# hail.net
KiCad netlist of a schematic drawn in EAGLE
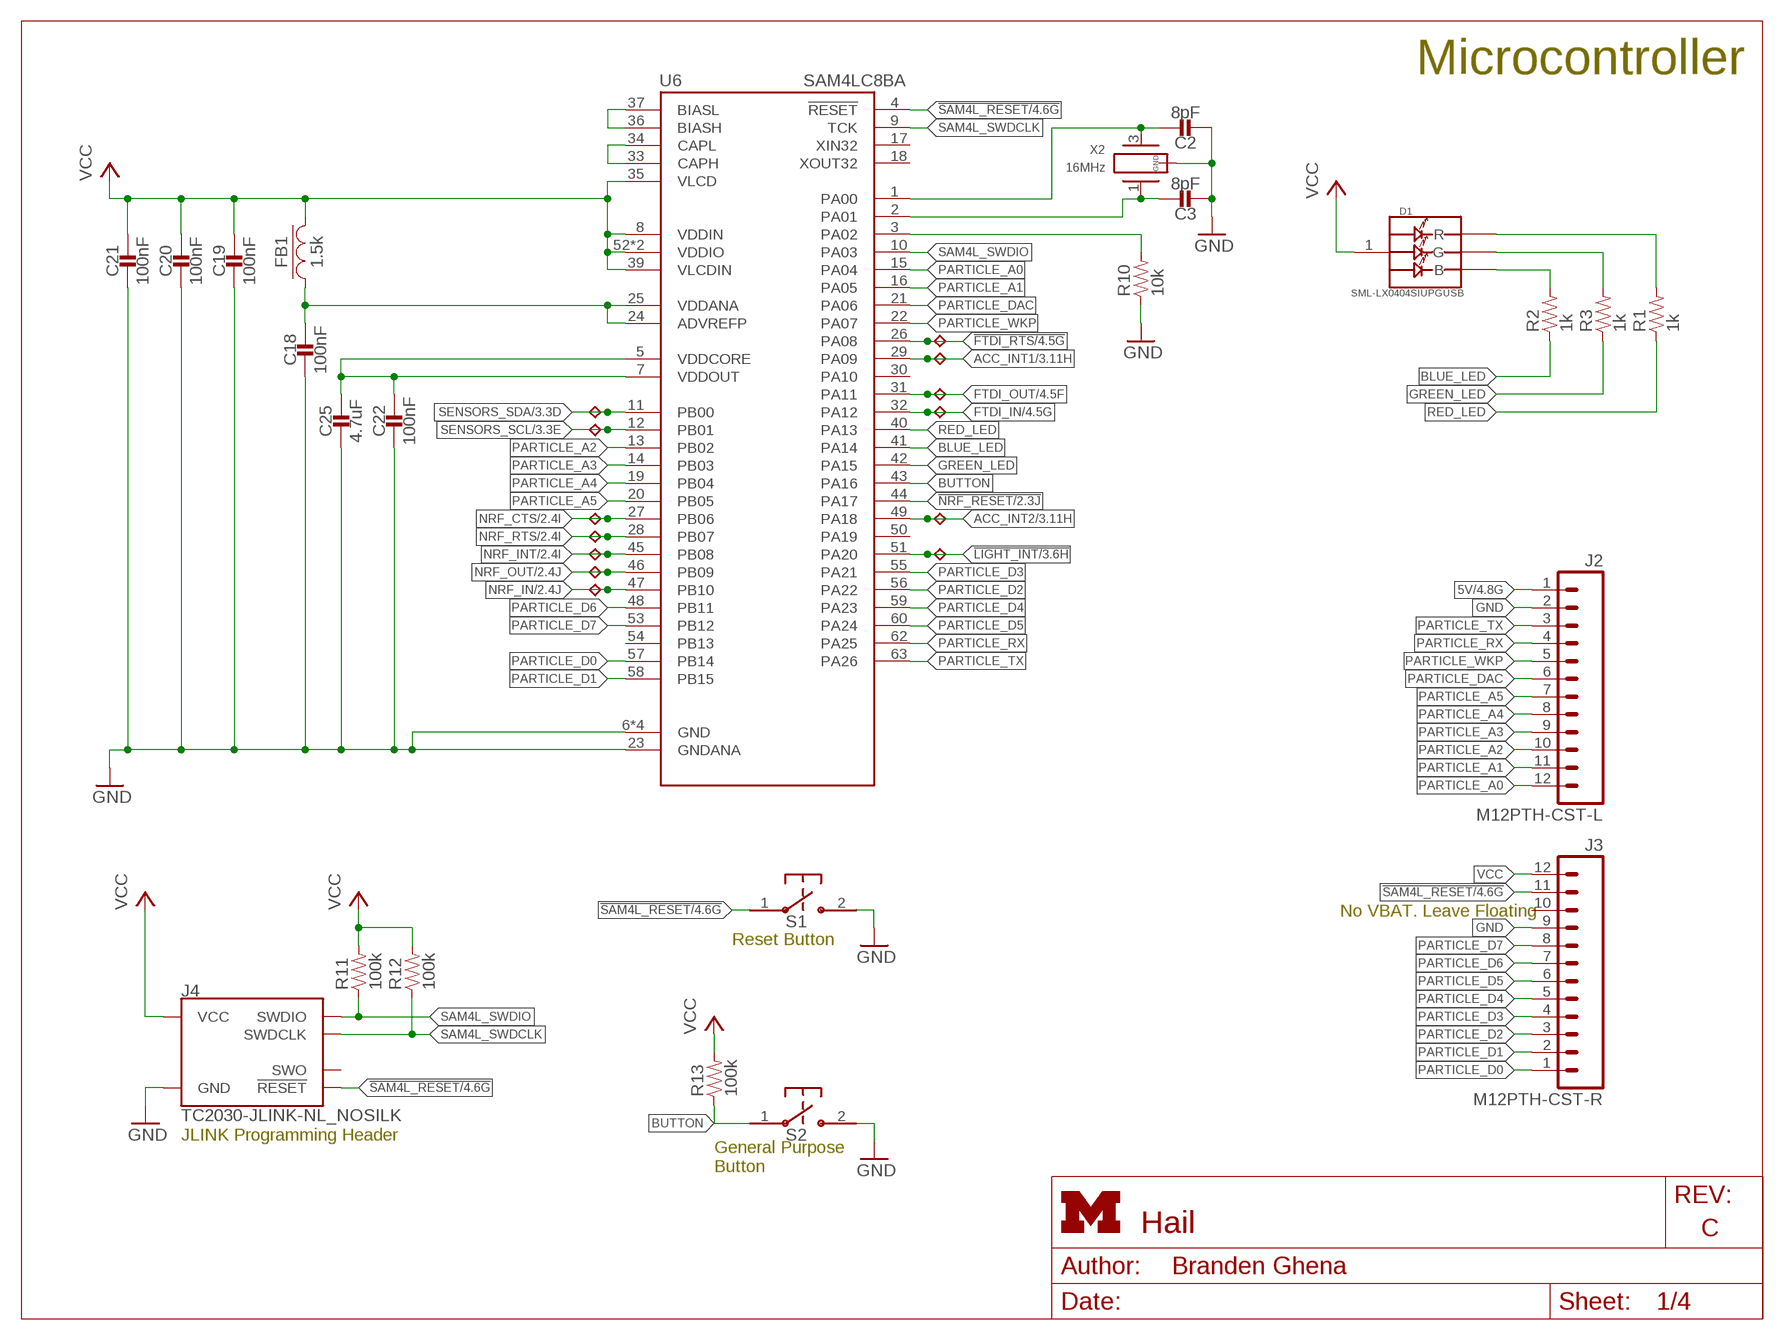
[diagram p0: schematic, sheet 1]
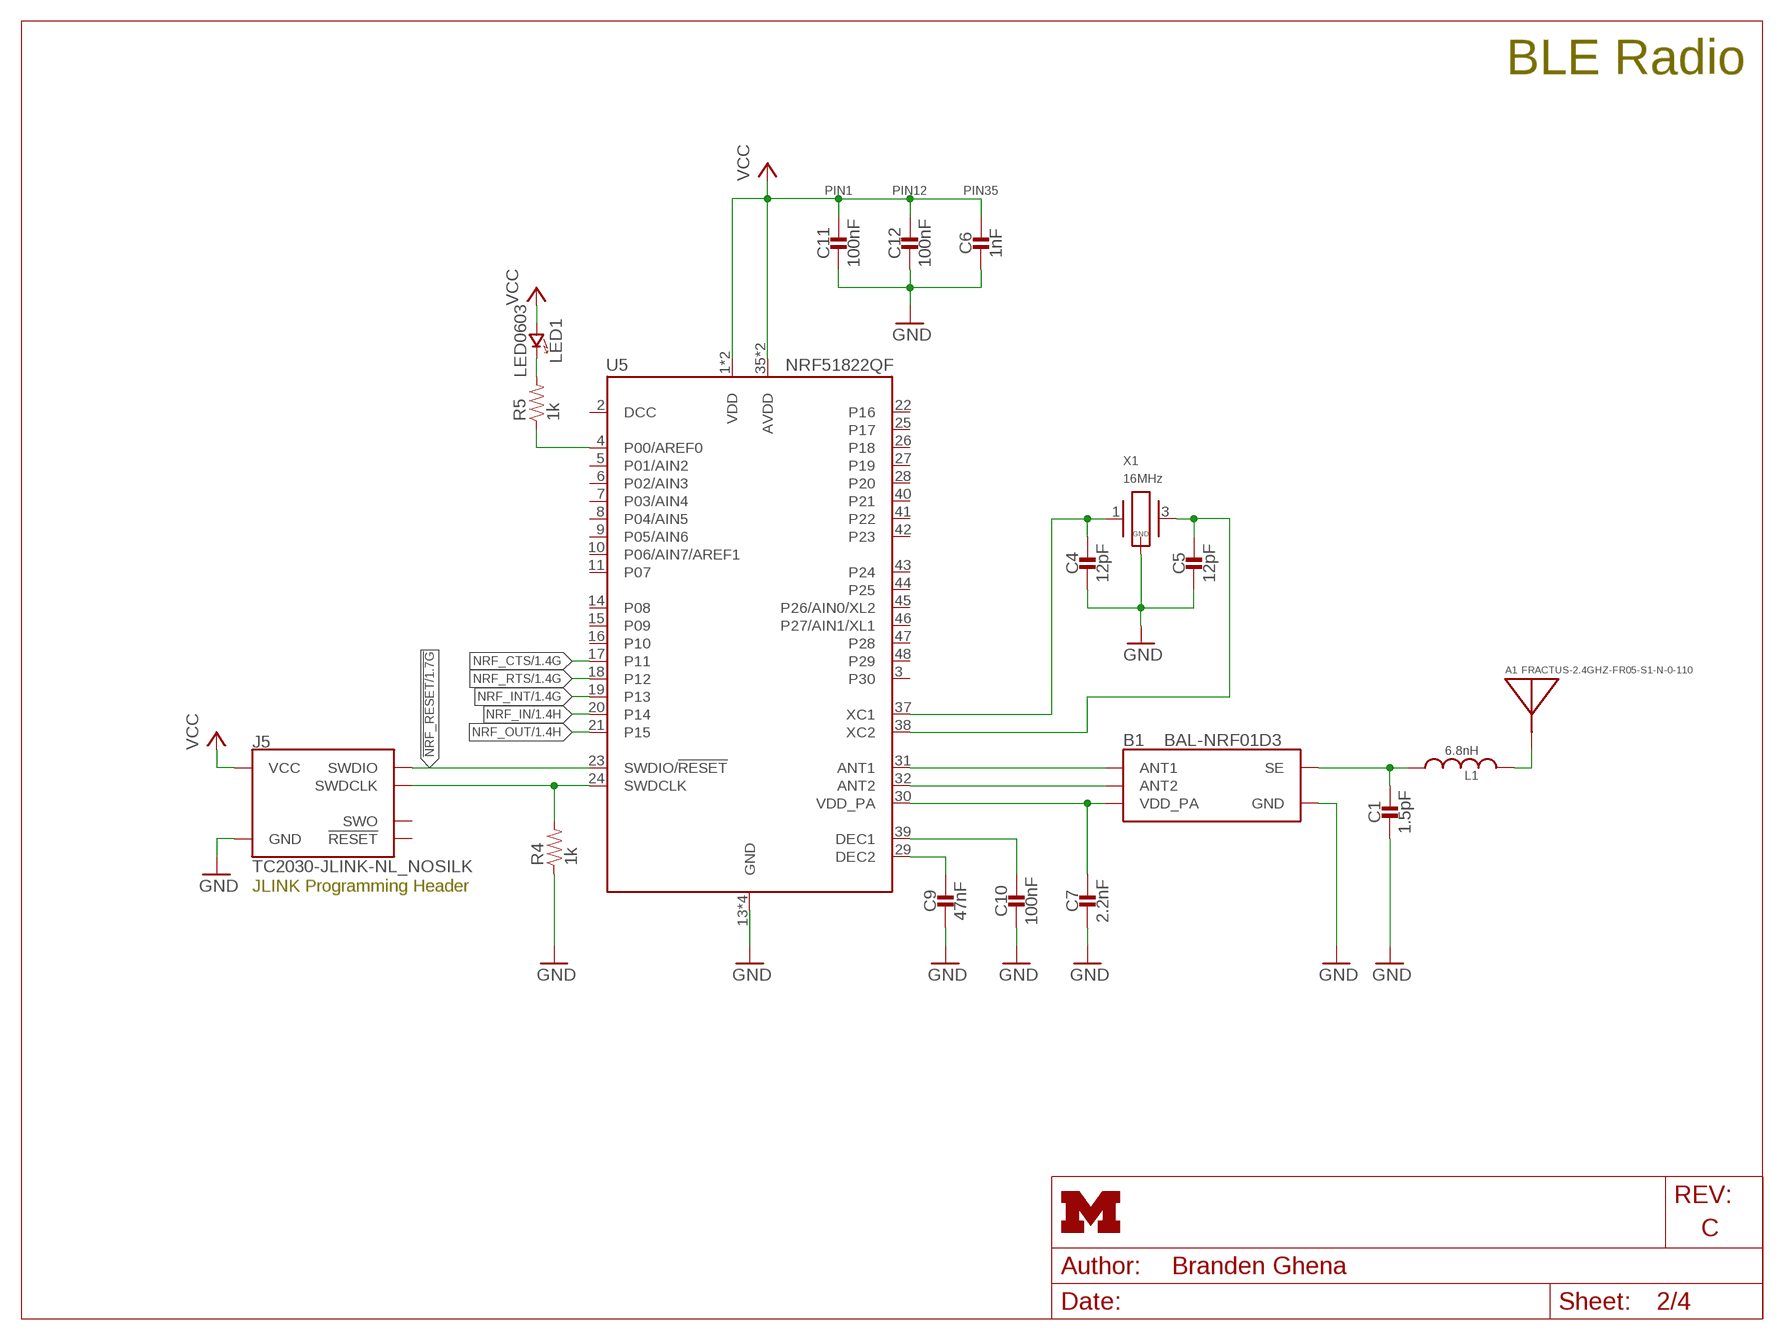
[diagram p1: schematic, sheet 2]
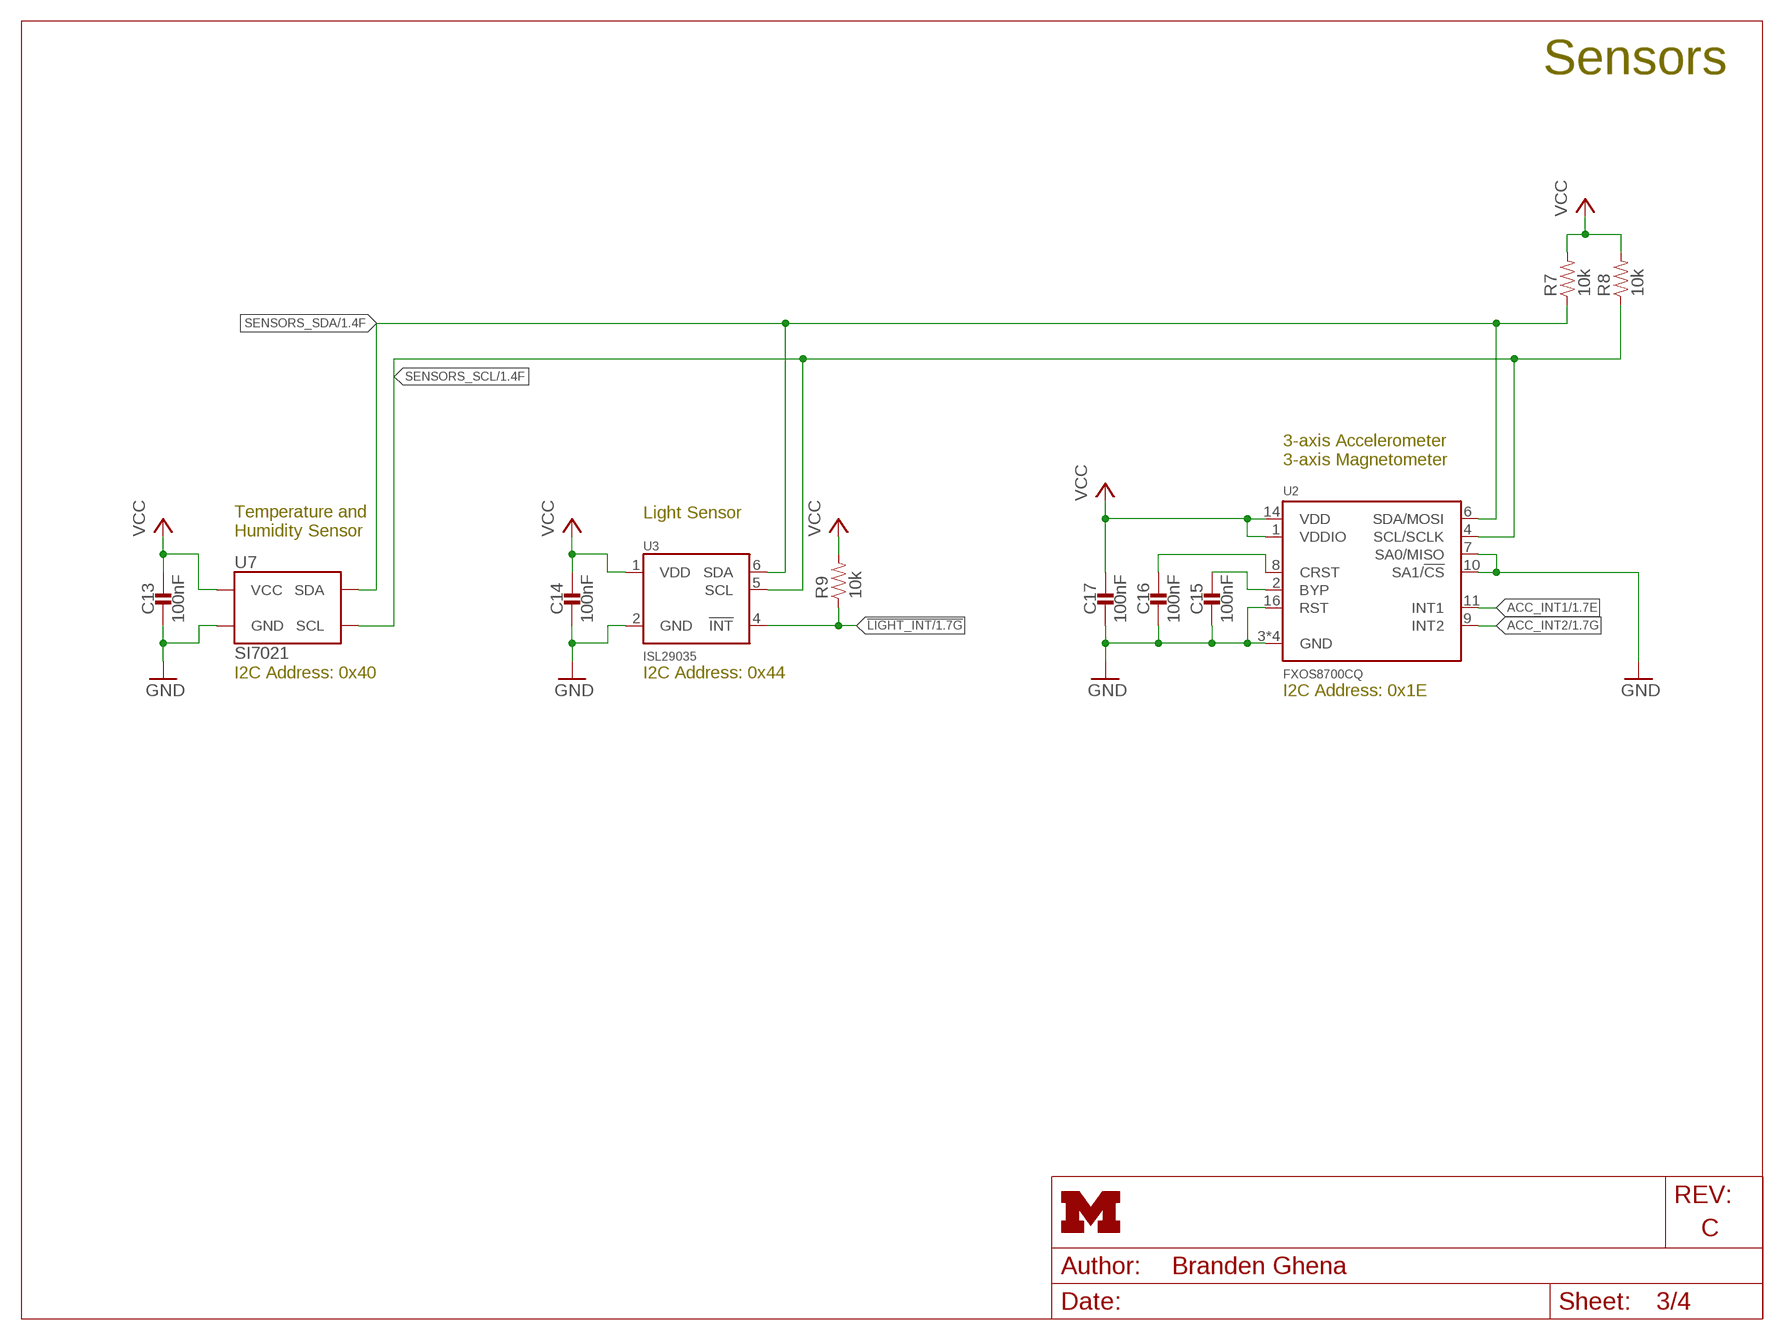
[diagram p2: schematic, sheet 3]
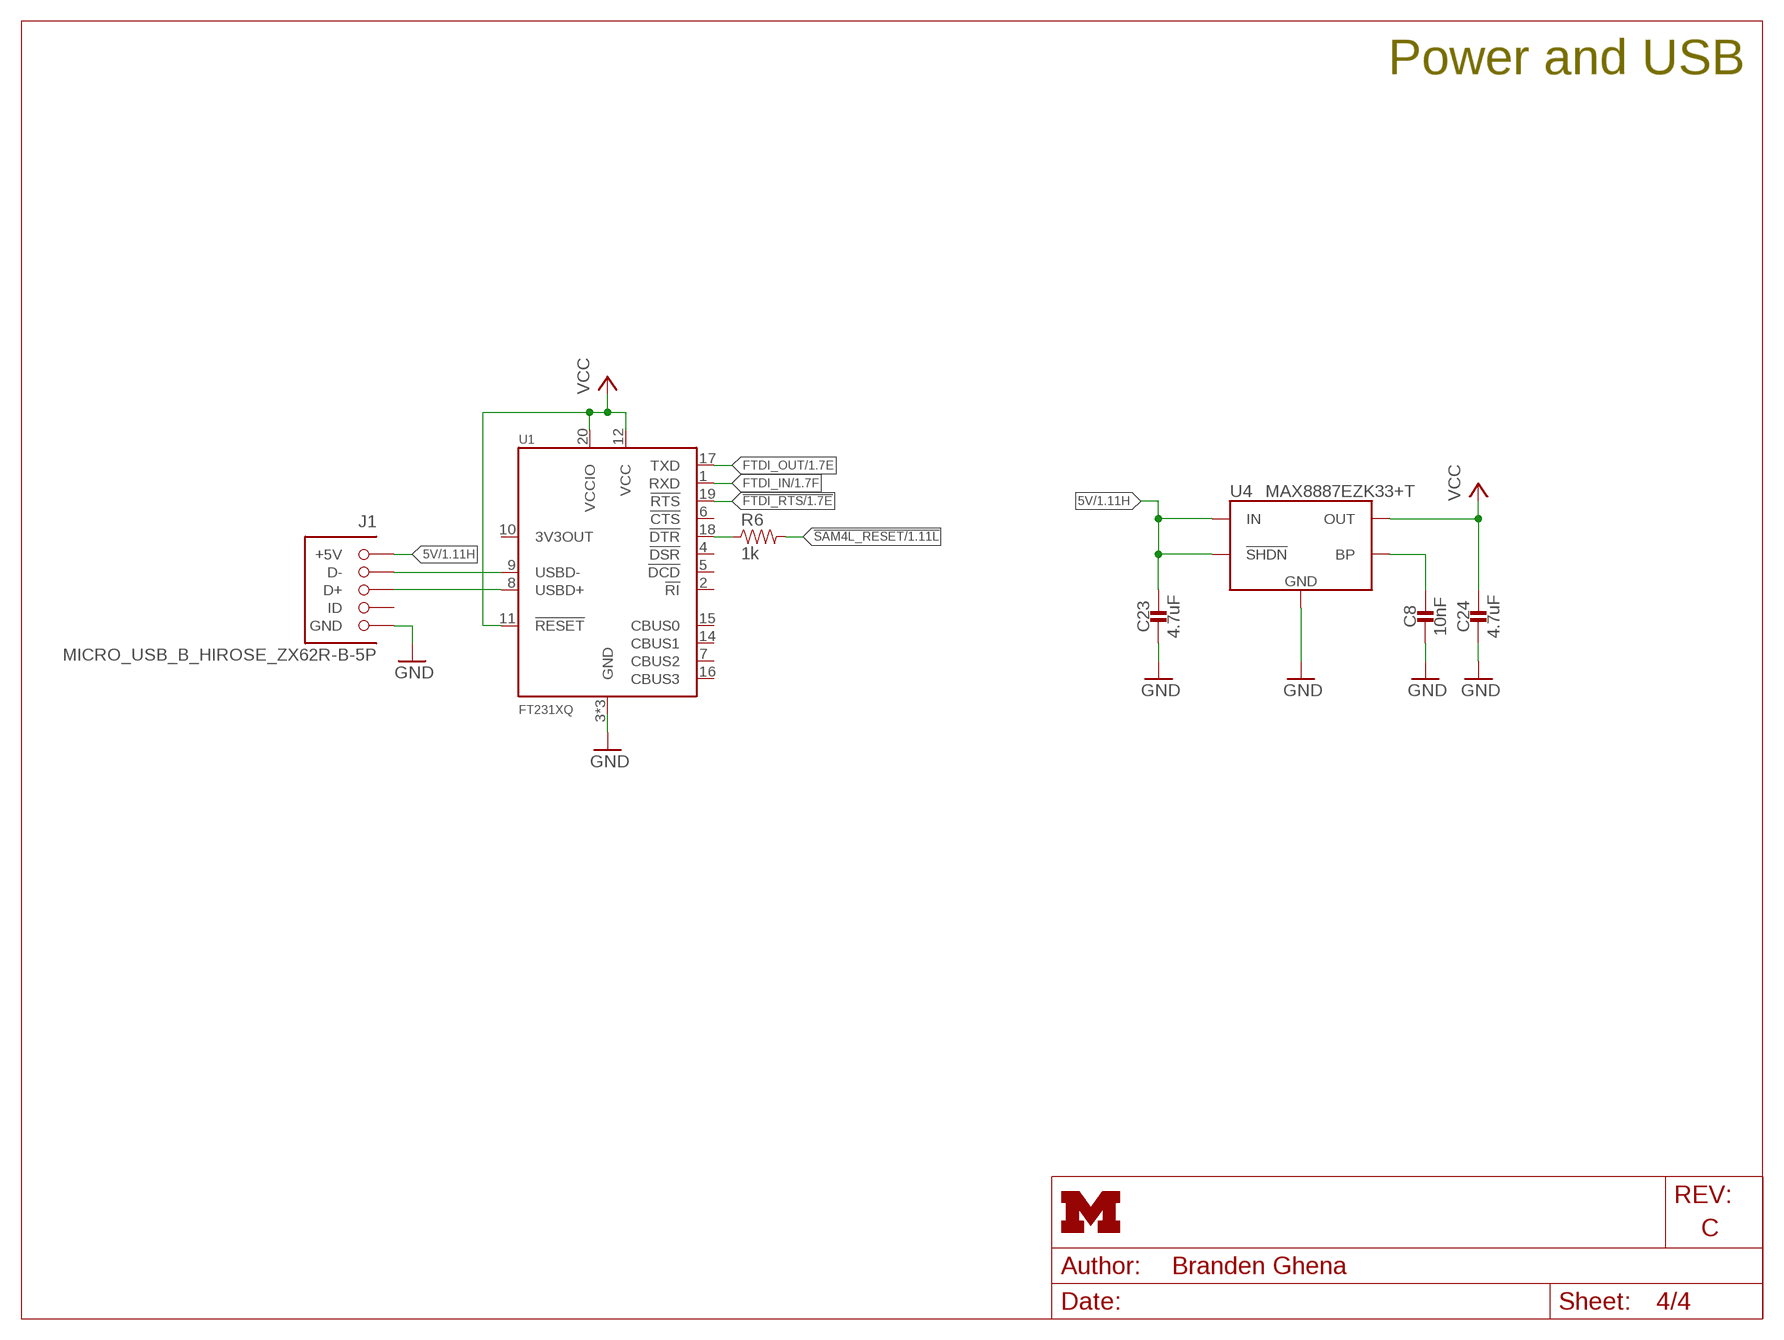
[diagram p3: schematic, sheet 4]

(export (version "E")
  (design (tool "Eeschema 10.0.6"))
  (components
    (comp (ref "C8")
      (value "10nF")
      (footprint "eagle-import:0402_CAP")
      (fields (field (name "MPN") "MF-CAP-0402-0.01uF"))
      (libsource (lib "eagle-import") (part "CAPACITOR0402_CAP"))
    )
    (comp (ref "C23")
      (value "4.7uF")
      (footprint "eagle-import:0402_CAP")
      (fields (field (name "MPN") "ZRB15XR61A475KE01D"))
      (libsource (lib "eagle-import") (part "CAPACITOR0402_CAP"))
    )
    (comp (ref "C24")
      (value "4.7uF")
      (footprint "eagle-import:0402_CAP")
      (fields (field (name "MPN") "ZRB15XR61A475KE01D"))
      (libsource (lib "eagle-import") (part "CAPACITOR0402_CAP"))
    )
    (comp (ref "J1")
      (value "MICRO_USB_B_HIROSE_ZX62R-B-5P")
      (footprint "eagle-import:USB_MICRO_B-HIROSE-ZX62R-B-5P")
      (fields (field (name "DIGIKEY") "H125274CT-ND") (field (name "MPN") "ZX62R-B-5P(30)"))
      (libsource (lib "eagle-import") (part "MICRO_USB_B_HIROSE_ZX62R-B-5P"))
    )
    (comp (ref "R6")
      (value "1k")
      (footprint "eagle-import:0402_RES")
      (fields (field (name "MPN") "MF-RES-0402-1K"))
      (libsource (lib "eagle-import") (part "RESISTOR0402_RES"))
    )
    (comp (ref "U1")
      (value "FT231XQ")
      (footprint "eagle-import:QFN-20-4MM")
      (fields (field (name "MPN") "FT231XQ-R"))
      (libsource (lib "eagle-import") (part "FT231XQ"))
    )
    (comp (ref "U4")
      (value "MAX8887EZK33+T")
      (footprint "eagle-import:SOT-23-5")
      (libsource (lib "eagle-import") (part "MAX8887EZK33+T"))
    )
    (comp (ref "C13")
      (value "100nF")
      (footprint "eagle-import:0402_CAP")
      (fields (field (name "MPN") "MF-CAP-0402-0.1uF"))
      (libsource (lib "eagle-import") (part "CAPACITOR0402_CAP"))
    )
    (comp (ref "C14")
      (value "100nF")
      (footprint "eagle-import:0402_CAP")
      (fields (field (name "MPN") "MF-CAP-0402-0.1uF"))
      (libsource (lib "eagle-import") (part "CAPACITOR0402_CAP"))
    )
    (comp (ref "C15")
      (value "100nF")
      (footprint "eagle-import:0402_CAP")
      (fields (field (name "MPN") "MF-CAP-0402-0.1uF"))
      (libsource (lib "eagle-import") (part "CAPACITOR0402_CAP"))
    )
    (comp (ref "C16")
      (value "100nF")
      (footprint "eagle-import:0402_CAP")
      (fields (field (name "MPN") "MF-CAP-0402-0.1uF"))
      (libsource (lib "eagle-import") (part "CAPACITOR0402_CAP"))
    )
    (comp (ref "C17")
      (value "100nF")
      (footprint "eagle-import:0402_CAP")
      (fields (field (name "MPN") "MF-CAP-0402-0.1uF"))
      (libsource (lib "eagle-import") (part "CAPACITOR0402_CAP"))
    )
    (comp (ref "R7")
      (value "10k")
      (footprint "eagle-import:0402_RES")
      (fields (field (name "MPN") "MF-RES-0402-10K"))
      (libsource (lib "eagle-import") (part "RESISTOR0402_RES"))
    )
    (comp (ref "R8")
      (value "10k")
      (footprint "eagle-import:0402_RES")
      (fields (field (name "MPN") "MF-RES-0402-10K"))
      (libsource (lib "eagle-import") (part "RESISTOR0402_RES"))
    )
    (comp (ref "R9")
      (value "10k")
      (footprint "eagle-import:0402_RES")
      (fields (field (name "MPN") "MF-RES-0402-10K"))
      (libsource (lib "eagle-import") (part "RESISTOR0402_RES"))
    )
    (comp (ref "U2")
      (value "FXOS8700CQ")
      (footprint "eagle-import:QFN-16-3MM")
      (fields (field (name "MPN") "FXOS8700CQR1"))
      (libsource (lib "eagle-import") (part "FXOS8700CQ"))
    )
    (comp (ref "U3")
      (value "ISL29035")
      (footprint "eagle-import:ODFN-6-1.5MMX1.6MM")
      (fields (field (name "MPN") "ISL29035IROZ-T7"))
      (libsource (lib "eagle-import") (part "ISL29035"))
    )
    (comp (ref "U7")
      (value "SI7021")
      (footprint "eagle-import:DFN-6_3MM")
      (fields (field (name "DIGIKEY") "336-3141-ND") (field (name "MPN") "SI7021-A20-GM1"))
      (libsource (lib "eagle-import") (part "SI7021"))
    )
    (comp (ref "A1")
      (value "FRACTUS-2.4GHZ-FR05-S1-N-0-110")
      (footprint "eagle-import:FRACTUS-ANTENNA-FR05-S1-N-0-110")
      (fields (field (name "MPN") "FR05-S1-N-0110B"))
      (libsource (lib "eagle-import") (part "FRACTUS-2.4GHZ-FR05-S1-N-0-110"))
    )
    (comp (ref "B1")
      (value "BAL-NRF01D3")
      (footprint "eagle-import:BAL-NRF01D3")
      (libsource (lib "eagle-import") (part "BAL-NRF01D3"))
    )
    (comp (ref "C1")
      (value "1.5pF")
      (footprint "eagle-import:0402_CAP")
      (fields (field (name "MPN") "GRM1555C1H1R5BA01D"))
      (libsource (lib "eagle-import") (part "CAPACITOR0402_CAP"))
    )
    (comp (ref "C4")
      (value "12pF")
      (footprint "eagle-import:0402_CAP")
      (fields (field (name "MPN") "GRM1555C1H120GA01D"))
      (libsource (lib "eagle-import") (part "CAPACITOR0402_CAP"))
    )
    (comp (ref "C5")
      (value "12pF")
      (footprint "eagle-import:0402_CAP")
      (fields (field (name "MPN") "GRM1555C1H120GA01D"))
      (libsource (lib "eagle-import") (part "CAPACITOR0402_CAP"))
    )
    (comp (ref "C6")
      (value "1nF")
      (footprint "eagle-import:0402_CAP")
      (fields (field (name "MPN") "MF-CAP-0402-1nF"))
      (libsource (lib "eagle-import") (part "CAPACITOR0402_CAP"))
    )
    (comp (ref "C7")
      (value "2.2nF")
      (footprint "eagle-import:0402_CAP")
      (fields (field (name "MPN") "GRM155R71E222KA01D"))
      (libsource (lib "eagle-import") (part "CAPACITOR0402_CAP"))
    )
    (comp (ref "C9")
      (value "47nF")
      (footprint "eagle-import:0402_CAP")
      (fields (field (name "MPN") "C1005X7R1C473K050BC"))
      (libsource (lib "eagle-import") (part "CAPACITOR0402_CAP"))
    )
    (comp (ref "C10")
      (value "100nF")
      (footprint "eagle-import:0402_CAP")
      (fields (field (name "MPN") "MF-CAP-0402-0.1uF"))
      (libsource (lib "eagle-import") (part "CAPACITOR0402_CAP"))
    )
    (comp (ref "C11")
      (value "100nF")
      (footprint "eagle-import:0402_CAP")
      (fields (field (name "MPN") "MF-CAP-0402-0.1uF"))
      (libsource (lib "eagle-import") (part "CAPACITOR0402_CAP"))
    )
    (comp (ref "C12")
      (value "100nF")
      (footprint "eagle-import:0402_CAP")
      (fields (field (name "MPN") "MF-CAP-0402-0.1uF"))
      (libsource (lib "eagle-import") (part "CAPACITOR0402_CAP"))
    )
    (comp (ref "J5")
      (value "TC2030-JLINK-NL_NOSILK")
      (footprint "eagle-import:TC2030-IDC-NL_NOSILK")
      (libsource (lib "eagle-import") (part "TC2030-JLINK-NL_NOSILK"))
    )
    (comp (ref "L1")
      (value "6.8nH")
      (footprint "eagle-import:0402_CAP")
      (fields (field (name "MPN") "LQW15AN6N8G00D"))
      (libsource (lib "eagle-import") (part "INDUCTOR0402"))
    )
    (comp (ref "LED1")
      (value "LED0603")
      (footprint "eagle-import:LED-0603")
      (fields (field (name "MPN") "MF-LED-0603-GREEN"))
      (libsource (lib "eagle-import") (part "LED0603"))
    )
    (comp (ref "R4")
      (value "1k")
      (footprint "eagle-import:0402_RES")
      (fields (field (name "MPN") "MF-RES-0402-1K"))
      (libsource (lib "eagle-import") (part "RESISTOR0402_RES"))
    )
    (comp (ref "R5")
      (value "1k")
      (footprint "eagle-import:0402_RES")
      (fields (field (name "MPN") "MF-RES-0402-1K"))
      (libsource (lib "eagle-import") (part "RESISTOR0402_RES"))
    )
    (comp (ref "U5")
      (value "NRF51822QF")
      (footprint "eagle-import:QFN-48-6MM")
      (fields (field (name "DIGIKEY") "1490-1049-1-ND") (field (name "MPN") "NRF51822-QFAC-R7"))
      (libsource (lib "eagle-import") (part "NRF51822QF"))
    )
    (comp (ref "X1")
      (value "16MHz")
      (footprint "eagle-import:TXC-8Y")
      (fields (field (name "MPN") "8Y-16.000MAAV-T"))
      (libsource (lib "eagle-import") (part "TXC-8Y"))
    )
    (comp (ref "C2")
      (value "8pF")
      (footprint "eagle-import:0402_CAP")
      (fields (field (name "MPN") "GRM1555C1H8R0BA01D"))
      (libsource (lib "eagle-import") (part "CAPACITOR0402_CAP"))
    )
    (comp (ref "C3")
      (value "8pF")
      (footprint "eagle-import:0402_CAP")
      (fields (field (name "MPN") "GRM1555C1H8R0BA01D"))
      (libsource (lib "eagle-import") (part "CAPACITOR0402_CAP"))
    )
    (comp (ref "C18")
      (value "100nF")
      (footprint "eagle-import:0402_CAP")
      (fields (field (name "MPN") "MF-CAP-0402-0.1uF"))
      (libsource (lib "eagle-import") (part "CAPACITOR0402_CAP"))
    )
    (comp (ref "C19")
      (value "100nF")
      (footprint "eagle-import:0402_CAP")
      (fields (field (name "MPN") "MF-CAP-0402-0.1uF"))
      (libsource (lib "eagle-import") (part "CAPACITOR0402_CAP"))
    )
    (comp (ref "C20")
      (value "100nF")
      (footprint "eagle-import:0402_CAP")
      (fields (field (name "MPN") "MF-CAP-0402-0.1uF"))
      (libsource (lib "eagle-import") (part "CAPACITOR0402_CAP"))
    )
    (comp (ref "C21")
      (value "100nF")
      (footprint "eagle-import:0402_CAP")
      (fields (field (name "MPN") "MF-CAP-0402-0.1uF"))
      (libsource (lib "eagle-import") (part "CAPACITOR0402_CAP"))
    )
    (comp (ref "C22")
      (value "100nF")
      (footprint "eagle-import:0402_CAP")
      (fields (field (name "MPN") "MF-CAP-0402-0.1uF"))
      (libsource (lib "eagle-import") (part "CAPACITOR0402_CAP"))
    )
    (comp (ref "C25")
      (value "4.7uF")
      (footprint "eagle-import:0402_CAP")
      (fields (field (name "MPN") "ZRB15XR61A475KE01D"))
      (libsource (lib "eagle-import") (part "CAPACITOR0402_CAP"))
    )
    (comp (ref "D1")
      (value "SML-LX0404SIUPGUSB")
      (footprint "eagle-import:1MM_SQ_4PAD")
      (libsource (lib "eagle-import") (part "SML-LX0404SIUPGUSB"))
    )
    (comp (ref "FB1")
      (value "1.5k")
      (footprint "eagle-import:0402_CAP")
      (fields (field (name "MPN") "CIM05J152NC"))
      (libsource (lib "eagle-import") (part "FERRITE_BEAD0402"))
    )
    (comp (ref "J2")
      (value "M12PTH-CST-L")
      (footprint "eagle-import:1X12-CASTELLATED")
      (fields (field (name "MPN") "MF-CON-2.54mm-01x12"))
      (libsource (lib "eagle-import") (part "M12PTH-CST-L"))
    )
    (comp (ref "J3")
      (value "M12PTH-CST-R")
      (footprint "eagle-import:1X12-CASTELLATED")
      (fields (field (name "MPN") "MF-CON-2.54mm-01x12"))
      (libsource (lib "eagle-import") (part "M12PTH-CST-R"))
    )
    (comp (ref "J4")
      (value "TC2030-JLINK-NL_NOSILK")
      (footprint "eagle-import:TC2030-IDC-NL_NOSILK")
      (libsource (lib "eagle-import") (part "TC2030-JLINK-NL_NOSILK"))
    )
    (comp (ref "R1")
      (value "1k")
      (footprint "eagle-import:0402_RES")
      (fields (field (name "MPN") "MF-RES-0402-1K"))
      (libsource (lib "eagle-import") (part "RESISTOR0402_RES"))
    )
    (comp (ref "R2")
      (value "1k")
      (footprint "eagle-import:0402_RES")
      (fields (field (name "MPN") "MF-RES-0402-1K"))
      (libsource (lib "eagle-import") (part "RESISTOR0402_RES"))
    )
    (comp (ref "R3")
      (value "1k")
      (footprint "eagle-import:0402_RES")
      (fields (field (name "MPN") "MF-RES-0402-1K"))
      (libsource (lib "eagle-import") (part "RESISTOR0402_RES"))
    )
    (comp (ref "R10")
      (value "10k")
      (footprint "eagle-import:0402_RES")
      (fields (field (name "MPN") "MF-RES-0402-10K"))
      (libsource (lib "eagle-import") (part "RESISTOR0402_RES"))
    )
    (comp (ref "R11")
      (value "100k")
      (footprint "eagle-import:0402_RES")
      (fields (field (name "MPN") "MF-RES-0402-100K"))
      (libsource (lib "eagle-import") (part "RESISTOR0402_RES"))
    )
    (comp (ref "R12")
      (value "100k")
      (footprint "eagle-import:0402_RES")
      (fields (field (name "MPN") "MF-RES-0402-100K"))
      (libsource (lib "eagle-import") (part "RESISTOR0402_RES"))
    )
    (comp (ref "R13")
      (value "100k")
      (footprint "eagle-import:0402_RES")
      (fields (field (name "MPN") "MF-RES-0402-100K"))
      (libsource (lib "eagle-import") (part "RESISTOR0402_RES"))
    )
    (comp (ref "S1")
      (value "B3U-1000P")
      (footprint "eagle-import:B3U-1000P")
      (libsource (lib "eagle-import") (part "B3U-1000P"))
    )
    (comp (ref "S2")
      (value "B3U-1000P")
      (footprint "eagle-import:B3U-1000P")
      (libsource (lib "eagle-import") (part "B3U-1000P"))
    )
    (comp (ref "TP1")
      (value "TPB1,27")
      (footprint "eagle-import:B1,27")
      (libsource (lib "eagle-import") (part "TPB1,27"))
    )
    (comp (ref "TP2")
      (value "TPB1,27")
      (footprint "eagle-import:B1,27")
      (libsource (lib "eagle-import") (part "TPB1,27"))
    )
    (comp (ref "TP3")
      (value "TPB1,27")
      (footprint "eagle-import:B1,27")
      (libsource (lib "eagle-import") (part "TPB1,27"))
    )
    (comp (ref "TP4")
      (value "TPB1,27")
      (footprint "eagle-import:B1,27")
      (libsource (lib "eagle-import") (part "TPB1,27"))
    )
    (comp (ref "TP5")
      (value "TPB1,27")
      (footprint "eagle-import:B1,27")
      (libsource (lib "eagle-import") (part "TPB1,27"))
    )
    (comp (ref "TP6")
      (value "TPB1,27")
      (footprint "eagle-import:B1,27")
      (libsource (lib "eagle-import") (part "TPB1,27"))
    )
    (comp (ref "TP7")
      (value "TPB1,27")
      (footprint "eagle-import:B1,27")
      (libsource (lib "eagle-import") (part "TPB1,27"))
    )
    (comp (ref "TP8")
      (value "TPB1,27")
      (footprint "eagle-import:B1,27")
      (libsource (lib "eagle-import") (part "TPB1,27"))
    )
    (comp (ref "TP9")
      (value "TPB1,27")
      (footprint "eagle-import:B1,27")
      (libsource (lib "eagle-import") (part "TPB1,27"))
    )
    (comp (ref "TP10")
      (value "TPB1,27")
      (footprint "eagle-import:B1,27")
      (libsource (lib "eagle-import") (part "TPB1,27"))
    )
    (comp (ref "TP11")
      (value "TPB1,27")
      (footprint "eagle-import:B1,27")
      (libsource (lib "eagle-import") (part "TPB1,27"))
    )
    (comp (ref "TP12")
      (value "TPB1,27")
      (footprint "eagle-import:B1,27")
      (libsource (lib "eagle-import") (part "TPB1,27"))
    )
    (comp (ref "TP13")
      (value "TPB1,27")
      (footprint "eagle-import:B1,27")
      (libsource (lib "eagle-import") (part "TPB1,27"))
    )
    (comp (ref "U6")
      (value "SAM4LC8BA")
      (footprint "eagle-import:QFN-64-9MM")
      (fields (field (name "DIGIKEY") "ATSAM4LC8BA-MURCT-ND") (field (name "MPN") "ATSAM4LC8BA-MU"))
      (libsource (lib "eagle-import") (part "SAM4LC8BA"))
    )
    (comp (ref "X2")
      (value "16MHz")
      (footprint "eagle-import:FHXXX")
      (fields (field (name "MPN") "FH1600015"))
      (libsource (lib "eagle-import") (part "FH1600015"))
    )
  )
  (nets
    (net (code "1") (name "5V") (class "Default")
      (node (ref "C23") (pin "1") (pinfunction "1_1") (pintype "bidirectional"))
      (node (ref "J1") (pin "1") (pinfunction "+5V_1") (pintype "bidirectional"))
      (node (ref "J2") (pin "1") (pinfunction "12_1") (pintype "passive"))
      (node (ref "U4") (pin "1") (pinfunction "IN_1") (pintype "bidirectional"))
      (node (ref "U4") (pin "3") (pinfunction "~{SHDN}_3") (pintype "bidirectional"))
    )
    (net (code "2") (name "ACC_INT1") (class "Default")
      (node (ref "TP8") (pin "TP") (pinfunction "TP_TP") (pintype "input"))
      (node (ref "U2") (pin "11") (pinfunction "INT1_11") (pintype "bidirectional"))
      (node (ref "U6") (pin "29") (pinfunction "PA09_29") (pintype "bidirectional"))
    )
    (net (code "3") (name "ACC_INT2") (class "Default")
      (node (ref "TP9") (pin "TP") (pinfunction "TP_TP") (pintype "input"))
      (node (ref "U2") (pin "9") (pinfunction "INT2_9") (pintype "bidirectional"))
      (node (ref "U6") (pin "49") (pinfunction "PA18_49") (pintype "bidirectional"))
    )
    (net (code "4") (name "BLUE_LED") (class "Default")
      (node (ref "R2") (pin "1") (pinfunction "1_1") (pintype "passive"))
      (node (ref "U6") (pin "41") (pinfunction "PA14_41") (pintype "bidirectional"))
    )
    (net (code "5") (name "BUTTON") (class "Default")
      (node (ref "R13") (pin "1") (pinfunction "1_1") (pintype "passive"))
      (node (ref "S2") (pin "1") (pinfunction "P$1_1") (pintype "passive"))
      (node (ref "U6") (pin "43") (pinfunction "PA16_43") (pintype "bidirectional"))
    )
    (net (code "6") (name "FTDI_IN") (class "Default")
      (node (ref "TP13") (pin "TP") (pinfunction "TP_TP") (pintype "input"))
      (node (ref "U1") (pin "1") (pinfunction "RXD_1") (pintype "bidirectional"))
      (node (ref "U6") (pin "32") (pinfunction "PA12_32") (pintype "bidirectional"))
    )
    (net (code "7") (name "FTDI_OUT") (class "Default")
      (node (ref "TP12") (pin "TP") (pinfunction "TP_TP") (pintype "input"))
      (node (ref "U1") (pin "17") (pinfunction "TXD_17") (pintype "bidirectional"))
      (node (ref "U6") (pin "31") (pinfunction "PA11_31") (pintype "bidirectional"))
    )
    (net (code "8") (name "GND") (class "Default")
      (node (ref "B1") (pin "GND") (pinfunction "GND_GND") (pintype "bidirectional"))
      (node (ref "C1") (pin "2") (pinfunction "2_2") (pintype "bidirectional"))
      (node (ref "C10") (pin "2") (pinfunction "2_2") (pintype "bidirectional"))
      (node (ref "C11") (pin "2") (pinfunction "2_2") (pintype "bidirectional"))
      (node (ref "C12") (pin "2") (pinfunction "2_2") (pintype "bidirectional"))
      (node (ref "C13") (pin "2") (pinfunction "2_2") (pintype "bidirectional"))
      (node (ref "C14") (pin "2") (pinfunction "2_2") (pintype "bidirectional"))
      (node (ref "C15") (pin "2") (pinfunction "2_2") (pintype "bidirectional"))
      (node (ref "C16") (pin "2") (pinfunction "2_2") (pintype "bidirectional"))
      (node (ref "C17") (pin "2") (pinfunction "2_2") (pintype "bidirectional"))
      (node (ref "C18") (pin "2") (pinfunction "2_2") (pintype "bidirectional"))
      (node (ref "C19") (pin "2") (pinfunction "2_2") (pintype "bidirectional"))
      (node (ref "C2") (pin "2") (pinfunction "2_2") (pintype "bidirectional"))
      (node (ref "C20") (pin "2") (pinfunction "2_2") (pintype "bidirectional"))
      (node (ref "C21") (pin "2") (pinfunction "2_2") (pintype "bidirectional"))
      (node (ref "C22") (pin "2") (pinfunction "2_2") (pintype "bidirectional"))
      (node (ref "C23") (pin "2") (pinfunction "2_2") (pintype "bidirectional"))
      (node (ref "C24") (pin "2") (pinfunction "2_2") (pintype "bidirectional"))
      (node (ref "C25") (pin "2") (pinfunction "2_2") (pintype "bidirectional"))
      (node (ref "C3") (pin "2") (pinfunction "2_2") (pintype "bidirectional"))
      (node (ref "C4") (pin "2") (pinfunction "2_2") (pintype "bidirectional"))
      (node (ref "C5") (pin "2") (pinfunction "2_2") (pintype "bidirectional"))
      (node (ref "C6") (pin "2") (pinfunction "2_2") (pintype "bidirectional"))
      (node (ref "C7") (pin "2") (pinfunction "2_2") (pintype "bidirectional"))
      (node (ref "C8") (pin "2") (pinfunction "2_2") (pintype "bidirectional"))
      (node (ref "C9") (pin "2") (pinfunction "2_2") (pintype "bidirectional"))
      (node (ref "J1") (pin "5") (pinfunction "GND_5") (pintype "bidirectional"))
      (node (ref "J2") (pin "2") (pinfunction "11_2") (pintype "passive"))
      (node (ref "J3") (pin "9") (pinfunction "9_9") (pintype "passive"))
      (node (ref "J4") (pin "5") (pinfunction "GND_5") (pintype "bidirectional"))
      (node (ref "J5") (pin "5") (pinfunction "GND_5") (pintype "bidirectional"))
      (node (ref "R10") (pin "1") (pinfunction "1_1") (pintype "passive"))
      (node (ref "R4") (pin "1") (pinfunction "1_1") (pintype "passive"))
      (node (ref "S1") (pin "2") (pinfunction "P$2_2") (pintype "passive"))
      (node (ref "S2") (pin "2") (pinfunction "P$2_2") (pintype "passive"))
      (node (ref "U1") (pin "13") (pinfunction "GND_13") (pintype "bidirectional"))
      (node (ref "U1") (pin "3") (pinfunction "GND_3") (pintype "bidirectional"))
      (node (ref "U1") (pin "GND") (pinfunction "GND_GND") (pintype "bidirectional"))
      (node (ref "U2") (pin "10") (pinfunction "SA1/~{CS}_10") (pintype "bidirectional"))
      (node (ref "U2") (pin "12") (pinfunction "GND_12") (pintype "bidirectional"))
      (node (ref "U2") (pin "13") (pinfunction "GND_13") (pintype "bidirectional"))
      (node (ref "U2") (pin "16") (pinfunction "RST_16") (pintype "bidirectional"))
      (node (ref "U2") (pin "3") (pinfunction "GND_3") (pintype "bidirectional"))
      (node (ref "U2") (pin "5") (pinfunction "GND_5") (pintype "bidirectional"))
      (node (ref "U2") (pin "7") (pinfunction "SA0/MISO_7") (pintype "bidirectional"))
      (node (ref "U3") (pin "2") (pinfunction "GND_2") (pintype "bidirectional"))
      (node (ref "U4") (pin "2") (pinfunction "GND_2") (pintype "bidirectional"))
      (node (ref "U5") (pin "13") (pinfunction "GND_13") (pintype "bidirectional"))
      (node (ref "U5") (pin "33") (pinfunction "GND_33") (pintype "bidirectional"))
      (node (ref "U5") (pin "34") (pinfunction "GND_34") (pintype "bidirectional"))
      (node (ref "U5") (pin "GND") (pinfunction "GND_GND") (pintype "bidirectional"))
      (node (ref "U6") (pin "23") (pinfunction "GNDANA_23") (pintype "power_in"))
      (node (ref "U6") (pin "38") (pinfunction "GND_38") (pintype "power_in"))
      (node (ref "U6") (pin "6") (pinfunction "GND_6") (pintype "power_in"))
      (node (ref "U6") (pin "64") (pinfunction "GND_64") (pintype "power_in"))
      (node (ref "U6") (pin "GND") (pinfunction "GND_GND") (pintype "power_in"))
      (node (ref "U7") (pin "2") (pinfunction "GND_2") (pintype "bidirectional"))
      (node (ref "X1") (pin "2") (pinfunction "GND_2") (pintype "bidirectional"))
      (node (ref "X1") (pin "4") (pinfunction "GND_4") (pintype "bidirectional"))
      (node (ref "X2") (pin "2") (pinfunction "GND_2") (pintype "bidirectional"))
      (node (ref "X2") (pin "4") (pinfunction "GND_4") (pintype "bidirectional"))
    )
    (net (code "9") (name "GREEN_LED") (class "Default")
      (node (ref "R3") (pin "1") (pinfunction "1_1") (pintype "passive"))
      (node (ref "U6") (pin "42") (pinfunction "PA15_42") (pintype "bidirectional"))
    )
    (net (code "10") (name "NRF_CTS") (class "Default")
      (node (ref "TP1") (pin "TP") (pinfunction "TP_TP") (pintype "input"))
      (node (ref "U5") (pin "17") (pinfunction "P11_17") (pintype "bidirectional"))
      (node (ref "U6") (pin "27") (pinfunction "PB06_27") (pintype "bidirectional"))
    )
    (net (code "11") (name "NRF_IN") (class "Default")
      (node (ref "TP5") (pin "TP") (pinfunction "TP_TP") (pintype "input"))
      (node (ref "U5") (pin "20") (pinfunction "P14_20") (pintype "bidirectional"))
      (node (ref "U6") (pin "47") (pinfunction "PB10_47") (pintype "bidirectional"))
    )
    (net (code "12") (name "NRF_INT") (class "Default")
      (node (ref "TP3") (pin "TP") (pinfunction "TP_TP") (pintype "input"))
      (node (ref "U5") (pin "19") (pinfunction "P13_19") (pintype "bidirectional"))
      (node (ref "U6") (pin "45") (pinfunction "PB08_45") (pintype "bidirectional"))
    )
    (net (code "13") (name "NRF_OUT") (class "Default")
      (node (ref "TP4") (pin "TP") (pinfunction "TP_TP") (pintype "input"))
      (node (ref "U5") (pin "21") (pinfunction "P15_21") (pintype "bidirectional"))
      (node (ref "U6") (pin "46") (pinfunction "PB09_46") (pintype "bidirectional"))
    )
    (net (code "14") (name "NRF_RTS") (class "Default")
      (node (ref "TP2") (pin "TP") (pinfunction "TP_TP") (pintype "input"))
      (node (ref "U5") (pin "18") (pinfunction "P12_18") (pintype "bidirectional"))
      (node (ref "U6") (pin "28") (pinfunction "PB07_28") (pintype "bidirectional"))
    )
    (net (code "15") (name "Net-(A1-ANTENNA)") (class "Default")
      (node (ref "A1") (pin "ANT") (pinfunction "ANTENNA_ANT") (pintype "bidirectional"))
      (node (ref "L1") (pin "2") (pinfunction "2_2") (pintype "bidirectional"))
    )
    (net (code "16") (name "Net-(B1-PadSE)") (class "Default")
      (node (ref "B1") (pin "SE") (pinfunction "SE_SE") (pintype "bidirectional"))
      (node (ref "C1") (pin "1") (pinfunction "1_1") (pintype "bidirectional"))
      (node (ref "L1") (pin "1") (pinfunction "1_1") (pintype "bidirectional"))
    )
    (net (code "17") (name "Net-(B1-VDD_PA)") (class "Default")
      (node (ref "B1") (pin "VCC") (pinfunction "VDD_PA_VCC") (pintype "bidirectional"))
      (node (ref "C7") (pin "1") (pinfunction "1_1") (pintype "bidirectional"))
      (node (ref "U5") (pin "30") (pinfunction "VDD_PA_30") (pintype "bidirectional"))
    )
    (net (code "18") (name "Net-(D1-B)") (class "Default")
      (node (ref "D1") (pin "3") (pinfunction "B_3") (pintype "output"))
      (node (ref "R2") (pin "2") (pinfunction "2_2") (pintype "passive"))
    )
    (net (code "19") (name "Net-(D1-G)") (class "Default")
      (node (ref "D1") (pin "4") (pinfunction "G_4") (pintype "output"))
      (node (ref "R3") (pin "2") (pinfunction "2_2") (pintype "passive"))
    )
    (net (code "20") (name "Net-(D1-R)") (class "Default")
      (node (ref "D1") (pin "2") (pinfunction "R_2") (pintype "output"))
      (node (ref "R1") (pin "2") (pinfunction "2_2") (pintype "passive"))
    )
    (net (code "21") (name "Net-(FB1-P$1)") (class "Default")
      (node (ref "C18") (pin "1") (pinfunction "1_1") (pintype "bidirectional"))
      (node (ref "FB1") (pin "1") (pinfunction "P$1_1") (pintype "bidirectional"))
      (node (ref "U6") (pin "24") (pinfunction "ADVREFP_24") (pintype "power_in"))
      (node (ref "U6") (pin "25") (pinfunction "VDDANA_25") (pintype "power_in"))
    )
    (net (code "22") (name "Net-(J1-D+)") (class "Default")
      (node (ref "J1") (pin "3") (pinfunction "D+_3") (pintype "bidirectional"))
      (node (ref "U1") (pin "8") (pinfunction "USBD+_8") (pintype "bidirectional"))
    )
    (net (code "23") (name "Net-(J1-D-)") (class "Default")
      (node (ref "J1") (pin "2") (pinfunction "D-_2") (pintype "bidirectional"))
      (node (ref "U1") (pin "9") (pinfunction "USBD-_9") (pintype "bidirectional"))
    )
    (net (code "24") (name "Net-(J5-SWDCLK)") (class "Default")
      (node (ref "J5") (pin "4") (pinfunction "SWDCLK_4") (pintype "bidirectional"))
      (node (ref "R4") (pin "2") (pinfunction "2_2") (pintype "passive"))
      (node (ref "U5") (pin "24") (pinfunction "SWDCLK_24") (pintype "bidirectional"))
    )
    (net (code "25") (name "Net-(LED1-CATHODE)") (class "Default")
      (node (ref "LED1") (pin "C") (pinfunction "CATHODE_C") (pintype "bidirectional"))
      (node (ref "R5") (pin "2") (pinfunction "2_2") (pintype "passive"))
    )
    (net (code "26") (name "Net-(U1-~{DTR})") (class "Default")
      (node (ref "R6") (pin "1") (pinfunction "1_1") (pintype "passive"))
      (node (ref "U1") (pin "18") (pinfunction "~{DTR}_18") (pintype "bidirectional"))
    )
    (net (code "27") (name "Net-(U2-BYP)") (class "Default")
      (node (ref "C15") (pin "1") (pinfunction "1_1") (pintype "bidirectional"))
      (node (ref "U2") (pin "2") (pinfunction "BYP_2") (pintype "bidirectional"))
    )
    (net (code "28") (name "Net-(U2-CRST)") (class "Default")
      (node (ref "C16") (pin "1") (pinfunction "1_1") (pintype "bidirectional"))
      (node (ref "U2") (pin "8") (pinfunction "CRST_8") (pintype "bidirectional"))
    )
    (net (code "29") (name "Net-(U4-BP)") (class "Default")
      (node (ref "C8") (pin "1") (pinfunction "1_1") (pintype "bidirectional"))
      (node (ref "U4") (pin "4") (pinfunction "BP_4") (pintype "bidirectional"))
    )
    (net (code "30") (name "Net-(U5-ANT1)") (class "Default")
      (node (ref "B1") (pin "ANT1") (pinfunction "ANT1_ANT1") (pintype "bidirectional"))
      (node (ref "U5") (pin "31") (pinfunction "ANT1_31") (pintype "bidirectional"))
    )
    (net (code "31") (name "Net-(U5-ANT2)") (class "Default")
      (node (ref "B1") (pin "ANT2") (pinfunction "ANT2_ANT2") (pintype "bidirectional"))
      (node (ref "U5") (pin "32") (pinfunction "ANT2_32") (pintype "bidirectional"))
    )
    (net (code "32") (name "Net-(U5-DEC1)") (class "Default")
      (node (ref "C10") (pin "1") (pinfunction "1_1") (pintype "bidirectional"))
      (node (ref "U5") (pin "39") (pinfunction "DEC1_39") (pintype "bidirectional"))
    )
    (net (code "33") (name "Net-(U5-DEC2)") (class "Default")
      (node (ref "C9") (pin "1") (pinfunction "1_1") (pintype "bidirectional"))
      (node (ref "U5") (pin "29") (pinfunction "DEC2_29") (pintype "bidirectional"))
    )
    (net (code "34") (name "Net-(U5-P00{slash}AREF0)") (class "Default")
      (node (ref "R5") (pin "1") (pinfunction "1_1") (pintype "passive"))
      (node (ref "U5") (pin "4") (pinfunction "P00/AREF0_4") (pintype "bidirectional"))
    )
    (net (code "35") (name "Net-(U5-XC1)") (class "Default")
      (node (ref "C4") (pin "1") (pinfunction "1_1") (pintype "bidirectional"))
      (node (ref "U5") (pin "37") (pinfunction "XC1_37") (pintype "bidirectional"))
      (node (ref "X1") (pin "1") (pinfunction "1_1") (pintype "bidirectional"))
    )
    (net (code "36") (name "Net-(U5-XC2)") (class "Default")
      (node (ref "C5") (pin "1") (pinfunction "1_1") (pintype "bidirectional"))
      (node (ref "U5") (pin "38") (pinfunction "XC2_38") (pintype "bidirectional"))
      (node (ref "X1") (pin "3") (pinfunction "2_3") (pintype "bidirectional"))
    )
    (net (code "37") (name "Net-(U6-BIASH)") (class "Default")
      (node (ref "U6") (pin "36") (pinfunction "BIASH_36") (pintype "bidirectional"))
      (node (ref "U6") (pin "37") (pinfunction "BIASL_37") (pintype "bidirectional"))
    )
    (net (code "38") (name "Net-(U6-CAPH)") (class "Default")
      (node (ref "U6") (pin "33") (pinfunction "CAPH_33") (pintype "bidirectional"))
      (node (ref "U6") (pin "34") (pinfunction "CAPL_34") (pintype "bidirectional"))
    )
    (net (code "39") (name "Net-(U6-PA00)") (class "Default")
      (node (ref "C2") (pin "1") (pinfunction "1_1") (pintype "bidirectional"))
      (node (ref "U6") (pin "1") (pinfunction "PA00_1") (pintype "bidirectional"))
      (node (ref "X2") (pin "3") (pinfunction "2_3") (pintype "bidirectional"))
    )
    (net (code "40") (name "Net-(U6-PA01)") (class "Default")
      (node (ref "C3") (pin "1") (pinfunction "1_1") (pintype "bidirectional"))
      (node (ref "U6") (pin "2") (pinfunction "PA01_2") (pintype "bidirectional"))
      (node (ref "X2") (pin "1") (pinfunction "1_1") (pintype "bidirectional"))
    )
    (net (code "41") (name "Net-(U6-PA02)") (class "Default")
      (node (ref "R10") (pin "2") (pinfunction "2_2") (pintype "passive"))
      (node (ref "U6") (pin "3") (pinfunction "PA02_3") (pintype "bidirectional"))
    )
    (net (code "42") (name "Net-(U6-VDDCORE)") (class "Default")
      (node (ref "C22") (pin "1") (pinfunction "1_1") (pintype "bidirectional"))
      (node (ref "C25") (pin "1") (pinfunction "1_1") (pintype "bidirectional"))
      (node (ref "U6") (pin "5") (pinfunction "VDDCORE_5") (pintype "power_in"))
      (node (ref "U6") (pin "7") (pinfunction "VDDOUT_7") (pintype "power_in"))
    )
    (net (code "43") (name "PARTICLE_A0") (class "Default")
      (node (ref "J2") (pin "12") (pinfunction "1_12") (pintype "passive"))
      (node (ref "U6") (pin "15") (pinfunction "PA04_15") (pintype "bidirectional"))
    )
    (net (code "44") (name "PARTICLE_A1") (class "Default")
      (node (ref "J2") (pin "11") (pinfunction "2_11") (pintype "passive"))
      (node (ref "U6") (pin "16") (pinfunction "PA05_16") (pintype "bidirectional"))
    )
    (net (code "45") (name "PARTICLE_A2") (class "Default")
      (node (ref "J2") (pin "10") (pinfunction "3_10") (pintype "passive"))
      (node (ref "U6") (pin "13") (pinfunction "PB02_13") (pintype "bidirectional"))
    )
    (net (code "46") (name "PARTICLE_A3") (class "Default")
      (node (ref "J2") (pin "9") (pinfunction "4_9") (pintype "passive"))
      (node (ref "U6") (pin "14") (pinfunction "PB03_14") (pintype "bidirectional"))
    )
    (net (code "47") (name "PARTICLE_A4") (class "Default")
      (node (ref "J2") (pin "8") (pinfunction "5_8") (pintype "passive"))
      (node (ref "U6") (pin "19") (pinfunction "PB04_19") (pintype "bidirectional"))
    )
    (net (code "48") (name "PARTICLE_A5") (class "Default")
      (node (ref "J2") (pin "7") (pinfunction "6_7") (pintype "passive"))
      (node (ref "U6") (pin "20") (pinfunction "PB05_20") (pintype "bidirectional"))
    )
    (net (code "49") (name "PARTICLE_D0") (class "Default")
      (node (ref "J3") (pin "1") (pinfunction "1_1") (pintype "passive"))
      (node (ref "U6") (pin "57") (pinfunction "PB14_57") (pintype "bidirectional"))
    )
    (net (code "50") (name "PARTICLE_D1") (class "Default")
      (node (ref "J3") (pin "2") (pinfunction "2_2") (pintype "passive"))
      (node (ref "U6") (pin "58") (pinfunction "PB15_58") (pintype "bidirectional"))
    )
    (net (code "51") (name "PARTICLE_D2") (class "Default")
      (node (ref "J3") (pin "3") (pinfunction "3_3") (pintype "passive"))
      (node (ref "U6") (pin "56") (pinfunction "PA22_56") (pintype "bidirectional"))
    )
    (net (code "52") (name "PARTICLE_D3") (class "Default")
      (node (ref "J3") (pin "4") (pinfunction "4_4") (pintype "passive"))
      (node (ref "U6") (pin "55") (pinfunction "PA21_55") (pintype "bidirectional"))
    )
    (net (code "53") (name "PARTICLE_D4") (class "Default")
      (node (ref "J3") (pin "5") (pinfunction "5_5") (pintype "passive"))
      (node (ref "U6") (pin "59") (pinfunction "PA23_59") (pintype "bidirectional"))
    )
    (net (code "54") (name "PARTICLE_D5") (class "Default")
      (node (ref "J3") (pin "6") (pinfunction "6_6") (pintype "passive"))
      (node (ref "U6") (pin "60") (pinfunction "PA24_60") (pintype "bidirectional"))
    )
    (net (code "55") (name "PARTICLE_D6") (class "Default")
      (node (ref "J3") (pin "7") (pinfunction "7_7") (pintype "passive"))
      (node (ref "U6") (pin "48") (pinfunction "PB11_48") (pintype "bidirectional"))
    )
    (net (code "56") (name "PARTICLE_D7") (class "Default")
      (node (ref "J3") (pin "8") (pinfunction "8_8") (pintype "passive"))
      (node (ref "U6") (pin "53") (pinfunction "PB12_53") (pintype "bidirectional"))
    )
    (net (code "57") (name "PARTICLE_DAC") (class "Default")
      (node (ref "J2") (pin "6") (pinfunction "7_6") (pintype "passive"))
      (node (ref "U6") (pin "21") (pinfunction "PA06_21") (pintype "bidirectional"))
    )
    (net (code "58") (name "PARTICLE_RX") (class "Default")
      (node (ref "J2") (pin "4") (pinfunction "9_4") (pintype "passive"))
      (node (ref "U6") (pin "62") (pinfunction "PA25_62") (pintype "bidirectional"))
    )
    (net (code "59") (name "PARTICLE_TX") (class "Default")
      (node (ref "J2") (pin "3") (pinfunction "10_3") (pintype "passive"))
      (node (ref "U6") (pin "63") (pinfunction "PA26_63") (pintype "bidirectional"))
    )
    (net (code "60") (name "PARTICLE_WKP") (class "Default")
      (node (ref "J2") (pin "5") (pinfunction "8_5") (pintype "passive"))
      (node (ref "U6") (pin "22") (pinfunction "PA07_22") (pintype "bidirectional"))
    )
    (net (code "61") (name "RED_LED") (class "Default")
      (node (ref "R1") (pin "1") (pinfunction "1_1") (pintype "passive"))
      (node (ref "U6") (pin "40") (pinfunction "PA13_40") (pintype "bidirectional"))
    )
    (net (code "62") (name "SAM4L_SWDCLK") (class "Default")
      (node (ref "J4") (pin "4") (pinfunction "SWDCLK_4") (pintype "bidirectional"))
      (node (ref "R12") (pin "1") (pinfunction "1_1") (pintype "passive"))
      (node (ref "U6") (pin "9") (pinfunction "TCK_9") (pintype "bidirectional"))
    )
    (net (code "63") (name "SAM4L_SWDIO") (class "Default")
      (node (ref "J4") (pin "2") (pinfunction "SWDIO_2") (pintype "bidirectional"))
      (node (ref "R11") (pin "1") (pinfunction "1_1") (pintype "passive"))
      (node (ref "U6") (pin "10") (pinfunction "PA03_10") (pintype "bidirectional"))
    )
    (net (code "64") (name "SENSORS_SCL") (class "Default")
      (node (ref "R8") (pin "1") (pinfunction "1_1") (pintype "passive"))
      (node (ref "TP7") (pin "TP") (pinfunction "TP_TP") (pintype "input"))
      (node (ref "U2") (pin "4") (pinfunction "SCL/SCLK_4") (pintype "bidirectional"))
      (node (ref "U3") (pin "5") (pinfunction "SCL_5") (pintype "bidirectional"))
      (node (ref "U6") (pin "12") (pinfunction "PB01_12") (pintype "bidirectional"))
      (node (ref "U7") (pin "6") (pinfunction "SCL_6") (pintype "bidirectional"))
    )
    (net (code "65") (name "SENSORS_SDA") (class "Default")
      (node (ref "R7") (pin "1") (pinfunction "1_1") (pintype "passive"))
      (node (ref "TP6") (pin "TP") (pinfunction "TP_TP") (pintype "input"))
      (node (ref "U2") (pin "6") (pinfunction "SDA/MOSI_6") (pintype "bidirectional"))
      (node (ref "U3") (pin "6") (pinfunction "SDA_6") (pintype "bidirectional"))
      (node (ref "U6") (pin "11") (pinfunction "PB00_11") (pintype "bidirectional"))
      (node (ref "U7") (pin "1") (pinfunction "SDA_1") (pintype "bidirectional"))
    )
    (net (code "66") (name "VCC") (class "Default")
      (node (ref "C11") (pin "1") (pinfunction "1_1") (pintype "bidirectional"))
      (node (ref "C12") (pin "1") (pinfunction "1_1") (pintype "bidirectional"))
      (node (ref "C13") (pin "1") (pinfunction "1_1") (pintype "bidirectional"))
      (node (ref "C14") (pin "1") (pinfunction "1_1") (pintype "bidirectional"))
      (node (ref "C17") (pin "1") (pinfunction "1_1") (pintype "bidirectional"))
      (node (ref "C19") (pin "1") (pinfunction "1_1") (pintype "bidirectional"))
      (node (ref "C20") (pin "1") (pinfunction "1_1") (pintype "bidirectional"))
      (node (ref "C21") (pin "1") (pinfunction "1_1") (pintype "bidirectional"))
      (node (ref "C24") (pin "1") (pinfunction "1_1") (pintype "bidirectional"))
      (node (ref "C6") (pin "1") (pinfunction "1_1") (pintype "bidirectional"))
      (node (ref "D1") (pin "1") (pinfunction "VDD_1") (pintype "bidirectional"))
      (node (ref "FB1") (pin "2") (pinfunction "P$2_2") (pintype "bidirectional"))
      (node (ref "J3") (pin "12") (pinfunction "12_12") (pintype "passive"))
      (node (ref "J4") (pin "1") (pinfunction "VCC_1") (pintype "bidirectional"))
      (node (ref "J5") (pin "1") (pinfunction "VCC_1") (pintype "bidirectional"))
      (node (ref "LED1") (pin "A") (pinfunction "ANODE_A") (pintype "bidirectional"))
      (node (ref "R11") (pin "2") (pinfunction "2_2") (pintype "passive"))
      (node (ref "R12") (pin "2") (pinfunction "2_2") (pintype "passive"))
      (node (ref "R13") (pin "2") (pinfunction "2_2") (pintype "passive"))
      (node (ref "R7") (pin "2") (pinfunction "2_2") (pintype "passive"))
      (node (ref "R8") (pin "2") (pinfunction "2_2") (pintype "passive"))
      (node (ref "R9") (pin "2") (pinfunction "2_2") (pintype "passive"))
      (node (ref "U1") (pin "11") (pinfunction "~{RESET}_11") (pintype "bidirectional"))
      (node (ref "U1") (pin "12") (pinfunction "VCC_12") (pintype "bidirectional"))
      (node (ref "U1") (pin "20") (pinfunction "VCCIO_20") (pintype "bidirectional"))
      (node (ref "U2") (pin "1") (pinfunction "VDDIO_1") (pintype "bidirectional"))
      (node (ref "U2") (pin "14") (pinfunction "VDD_14") (pintype "bidirectional"))
      (node (ref "U3") (pin "1") (pinfunction "VDD_1") (pintype "bidirectional"))
      (node (ref "U4") (pin "5") (pinfunction "OUT_5") (pintype "bidirectional"))
      (node (ref "U5") (pin "1") (pinfunction "VDD_1") (pintype "bidirectional"))
      (node (ref "U5") (pin "12") (pinfunction "VDD_12") (pintype "bidirectional"))
      (node (ref "U5") (pin "35") (pinfunction "AVDD_35") (pintype "bidirectional"))
      (node (ref "U5") (pin "36") (pinfunction "AVDD_36") (pintype "bidirectional"))
      (node (ref "U6") (pin "35") (pinfunction "VLCD_35") (pintype "bidirectional"))
      (node (ref "U6") (pin "39") (pinfunction "VLCDIN_39") (pintype "power_in"))
      (node (ref "U6") (pin "52") (pinfunction "VDDIO_52") (pintype "power_in"))
      (node (ref "U6") (pin "61") (pinfunction "VDDIO_61") (pintype "power_in"))
      (node (ref "U6") (pin "8") (pinfunction "VDDIN_8") (pintype "power_in"))
      (node (ref "U7") (pin "5") (pinfunction "VCC_5") (pintype "bidirectional"))
    )
    (net (code "67") (name "unconnected-(J1-ID-Pad4)") (class "Default")
      (node (ref "J1") (pin "4") (pinfunction "ID_4") (pintype "bidirectional"))
    )
    (net (code "68") (name "unconnected-(J3-Pad10)") (class "Default")
      (node (ref "J3") (pin "10") (pinfunction "10_10") (pintype "passive"))
    )
    (net (code "69") (name "unconnected-(J4-SWO-Pad6)") (class "Default")
      (node (ref "J4") (pin "6") (pinfunction "SWO_6") (pintype "bidirectional"))
    )
    (net (code "70") (name "unconnected-(J5-SWO-Pad6)") (class "Default")
      (node (ref "J5") (pin "6") (pinfunction "SWO_6") (pintype "bidirectional"))
    )
    (net (code "71") (name "unconnected-(J5-~{RESET}-Pad3)") (class "Default")
      (node (ref "J5") (pin "3") (pinfunction "~{RESET}_3") (pintype "bidirectional"))
    )
    (net (code "72") (name "unconnected-(U1-3V3OUT-Pad10)") (class "Default")
      (node (ref "U1") (pin "10") (pinfunction "3V3OUT_10") (pintype "bidirectional"))
    )
    (net (code "73") (name "unconnected-(U1-CBUS0-Pad15)") (class "Default")
      (node (ref "U1") (pin "15") (pinfunction "CBUS0_15") (pintype "bidirectional"))
    )
    (net (code "74") (name "unconnected-(U1-CBUS1-Pad14)") (class "Default")
      (node (ref "U1") (pin "14") (pinfunction "CBUS1_14") (pintype "bidirectional"))
    )
    (net (code "75") (name "unconnected-(U1-CBUS2-Pad7)") (class "Default")
      (node (ref "U1") (pin "7") (pinfunction "CBUS2_7") (pintype "bidirectional"))
    )
    (net (code "76") (name "unconnected-(U1-CBUS3-Pad16)") (class "Default")
      (node (ref "U1") (pin "16") (pinfunction "CBUS3_16") (pintype "bidirectional"))
    )
    (net (code "77") (name "unconnected-(U1-~{CTS}-Pad6)") (class "Default")
      (node (ref "U1") (pin "6") (pinfunction "~{CTS}_6") (pintype "bidirectional"))
    )
    (net (code "78") (name "unconnected-(U1-~{DCD}-Pad5)") (class "Default")
      (node (ref "U1") (pin "5") (pinfunction "~{DCD}_5") (pintype "bidirectional"))
    )
    (net (code "79") (name "unconnected-(U1-~{DSR}-Pad4)") (class "Default")
      (node (ref "U1") (pin "4") (pinfunction "~{DSR}_4") (pintype "bidirectional"))
    )
    (net (code "80") (name "unconnected-(U1-~{RI}-Pad2)") (class "Default")
      (node (ref "U1") (pin "2") (pinfunction "~{RI}_2") (pintype "bidirectional"))
    )
    (net (code "81") (name "unconnected-(U5-DCC-Pad2)") (class "Default")
      (node (ref "U5") (pin "2") (pinfunction "DCC_2") (pintype "bidirectional"))
    )
    (net (code "82") (name "unconnected-(U5-P01{slash}AIN2-Pad5)") (class "Default")
      (node (ref "U5") (pin "5") (pinfunction "P01/AIN2_5") (pintype "bidirectional"))
    )
    (net (code "83") (name "unconnected-(U5-P02{slash}AIN3-Pad6)") (class "Default")
      (node (ref "U5") (pin "6") (pinfunction "P02/AIN3_6") (pintype "bidirectional"))
    )
    (net (code "84") (name "unconnected-(U5-P03{slash}AIN4-Pad7)") (class "Default")
      (node (ref "U5") (pin "7") (pinfunction "P03/AIN4_7") (pintype "bidirectional"))
    )
    (net (code "85") (name "unconnected-(U5-P04{slash}AIN5-Pad8)") (class "Default")
      (node (ref "U5") (pin "8") (pinfunction "P04/AIN5_8") (pintype "bidirectional"))
    )
    (net (code "86") (name "unconnected-(U5-P05{slash}AIN6-Pad9)") (class "Default")
      (node (ref "U5") (pin "9") (pinfunction "P05/AIN6_9") (pintype "bidirectional"))
    )
    (net (code "87") (name "unconnected-(U5-P06{slash}AIN7{slash}AREF1-Pad10)") (class "Default")
      (node (ref "U5") (pin "10") (pinfunction "P06/AIN7/AREF1_10") (pintype "bidirectional"))
    )
    (net (code "88") (name "unconnected-(U5-P07-Pad11)") (class "Default")
      (node (ref "U5") (pin "11") (pinfunction "P07_11") (pintype "bidirectional"))
    )
    (net (code "89") (name "unconnected-(U5-P08-Pad14)") (class "Default")
      (node (ref "U5") (pin "14") (pinfunction "P08_14") (pintype "bidirectional"))
    )
    (net (code "90") (name "unconnected-(U5-P09-Pad15)") (class "Default")
      (node (ref "U5") (pin "15") (pinfunction "P09_15") (pintype "bidirectional"))
    )
    (net (code "91") (name "unconnected-(U5-P10-Pad16)") (class "Default")
      (node (ref "U5") (pin "16") (pinfunction "P10_16") (pintype "bidirectional"))
    )
    (net (code "92") (name "unconnected-(U5-P16-Pad22)") (class "Default")
      (node (ref "U5") (pin "22") (pinfunction "P16_22") (pintype "bidirectional"))
    )
    (net (code "93") (name "unconnected-(U5-P17-Pad25)") (class "Default")
      (node (ref "U5") (pin "25") (pinfunction "P17_25") (pintype "bidirectional"))
    )
    (net (code "94") (name "unconnected-(U5-P18-Pad26)") (class "Default")
      (node (ref "U5") (pin "26") (pinfunction "P18_26") (pintype "bidirectional"))
    )
    (net (code "95") (name "unconnected-(U5-P19-Pad27)") (class "Default")
      (node (ref "U5") (pin "27") (pinfunction "P19_27") (pintype "bidirectional"))
    )
    (net (code "96") (name "unconnected-(U5-P20-Pad28)") (class "Default")
      (node (ref "U5") (pin "28") (pinfunction "P20_28") (pintype "bidirectional"))
    )
    (net (code "97") (name "unconnected-(U5-P21-Pad40)") (class "Default")
      (node (ref "U5") (pin "40") (pinfunction "P21_40") (pintype "bidirectional"))
    )
    (net (code "98") (name "unconnected-(U5-P22-Pad41)") (class "Default")
      (node (ref "U5") (pin "41") (pinfunction "P22_41") (pintype "bidirectional"))
    )
    (net (code "99") (name "unconnected-(U5-P23-Pad42)") (class "Default")
      (node (ref "U5") (pin "42") (pinfunction "P23_42") (pintype "bidirectional"))
    )
    (net (code "100") (name "unconnected-(U5-P24-Pad43)") (class "Default")
      (node (ref "U5") (pin "43") (pinfunction "P24_43") (pintype "bidirectional"))
    )
    (net (code "101") (name "unconnected-(U5-P25-Pad44)") (class "Default")
      (node (ref "U5") (pin "44") (pinfunction "P25_44") (pintype "bidirectional"))
    )
    (net (code "102") (name "unconnected-(U5-P26{slash}AIN0{slash}XL2-Pad45)") (class "Default")
      (node (ref "U5") (pin "45") (pinfunction "P26/AIN0/XL2_45") (pintype "bidirectional"))
    )
    (net (code "103") (name "unconnected-(U5-P27{slash}AIN1{slash}XL1-Pad46)") (class "Default")
      (node (ref "U5") (pin "46") (pinfunction "P27/AIN1/XL1_46") (pintype "bidirectional"))
    )
    (net (code "104") (name "unconnected-(U5-P28-Pad47)") (class "Default")
      (node (ref "U5") (pin "47") (pinfunction "P28_47") (pintype "bidirectional"))
    )
    (net (code "105") (name "unconnected-(U5-P29-Pad48)") (class "Default")
      (node (ref "U5") (pin "48") (pinfunction "P29_48") (pintype "bidirectional"))
    )
    (net (code "106") (name "unconnected-(U5-P30-Pad3)") (class "Default")
      (node (ref "U5") (pin "3") (pinfunction "P30_3") (pintype "bidirectional"))
    )
    (net (code "107") (name "unconnected-(U6-PA10-Pad30)") (class "Default")
      (node (ref "U6") (pin "30") (pinfunction "PA10_30") (pintype "bidirectional"))
    )
    (net (code "108") (name "unconnected-(U6-PA19-Pad50)") (class "Default")
      (node (ref "U6") (pin "50") (pinfunction "PA19_50") (pintype "bidirectional"))
    )
    (net (code "109") (name "unconnected-(U6-PB13-Pad54)") (class "Default")
      (node (ref "U6") (pin "54") (pinfunction "PB13_54") (pintype "bidirectional"))
    )
    (net (code "110") (name "unconnected-(U6-XIN32-Pad17)") (class "Default")
      (node (ref "U6") (pin "17") (pinfunction "XIN32_17") (pintype "bidirectional"))
    )
    (net (code "111") (name "unconnected-(U6-XOUT32-Pad18)") (class "Default")
      (node (ref "U6") (pin "18") (pinfunction "XOUT32_18") (pintype "bidirectional"))
    )
    (net (code "112") (name "~{FTDI_RTS}") (class "Default")
      (node (ref "TP11") (pin "TP") (pinfunction "TP_TP") (pintype "input"))
      (node (ref "U1") (pin "19") (pinfunction "~{RTS}_19") (pintype "bidirectional"))
      (node (ref "U6") (pin "26") (pinfunction "PA08_26") (pintype "bidirectional"))
    )
    (net (code "113") (name "~{LIGHT_INT}") (class "Default")
      (node (ref "R9") (pin "1") (pinfunction "1_1") (pintype "passive"))
      (node (ref "TP10") (pin "TP") (pinfunction "TP_TP") (pintype "input"))
      (node (ref "U3") (pin "4") (pinfunction "~{INT}_4") (pintype "bidirectional"))
      (node (ref "U6") (pin "51") (pinfunction "PA20_51") (pintype "bidirectional"))
    )
    (net (code "114") (name "~{NRF_RESET}") (class "Default")
      (node (ref "J5") (pin "2") (pinfunction "SWDIO_2") (pintype "bidirectional"))
      (node (ref "U5") (pin "23") (pinfunction "SWDIO/~{RESET}_23") (pintype "bidirectional"))
      (node (ref "U6") (pin "44") (pinfunction "PA17_44") (pintype "bidirectional"))
    )
    (net (code "115") (name "~{SAM4L_RESET}") (class "Default")
      (node (ref "J3") (pin "11") (pinfunction "11_11") (pintype "passive"))
      (node (ref "J4") (pin "3") (pinfunction "~{RESET}_3") (pintype "bidirectional"))
      (node (ref "R6") (pin "2") (pinfunction "2_2") (pintype "passive"))
      (node (ref "S1") (pin "1") (pinfunction "P$1_1") (pintype "passive"))
      (node (ref "U6") (pin "4") (pinfunction "~{RESET}_4") (pintype "bidirectional"))
    )
  )
)
